# RFM69HW_SMA.net
KiCad netlist of a schematic drawn in EAGLE
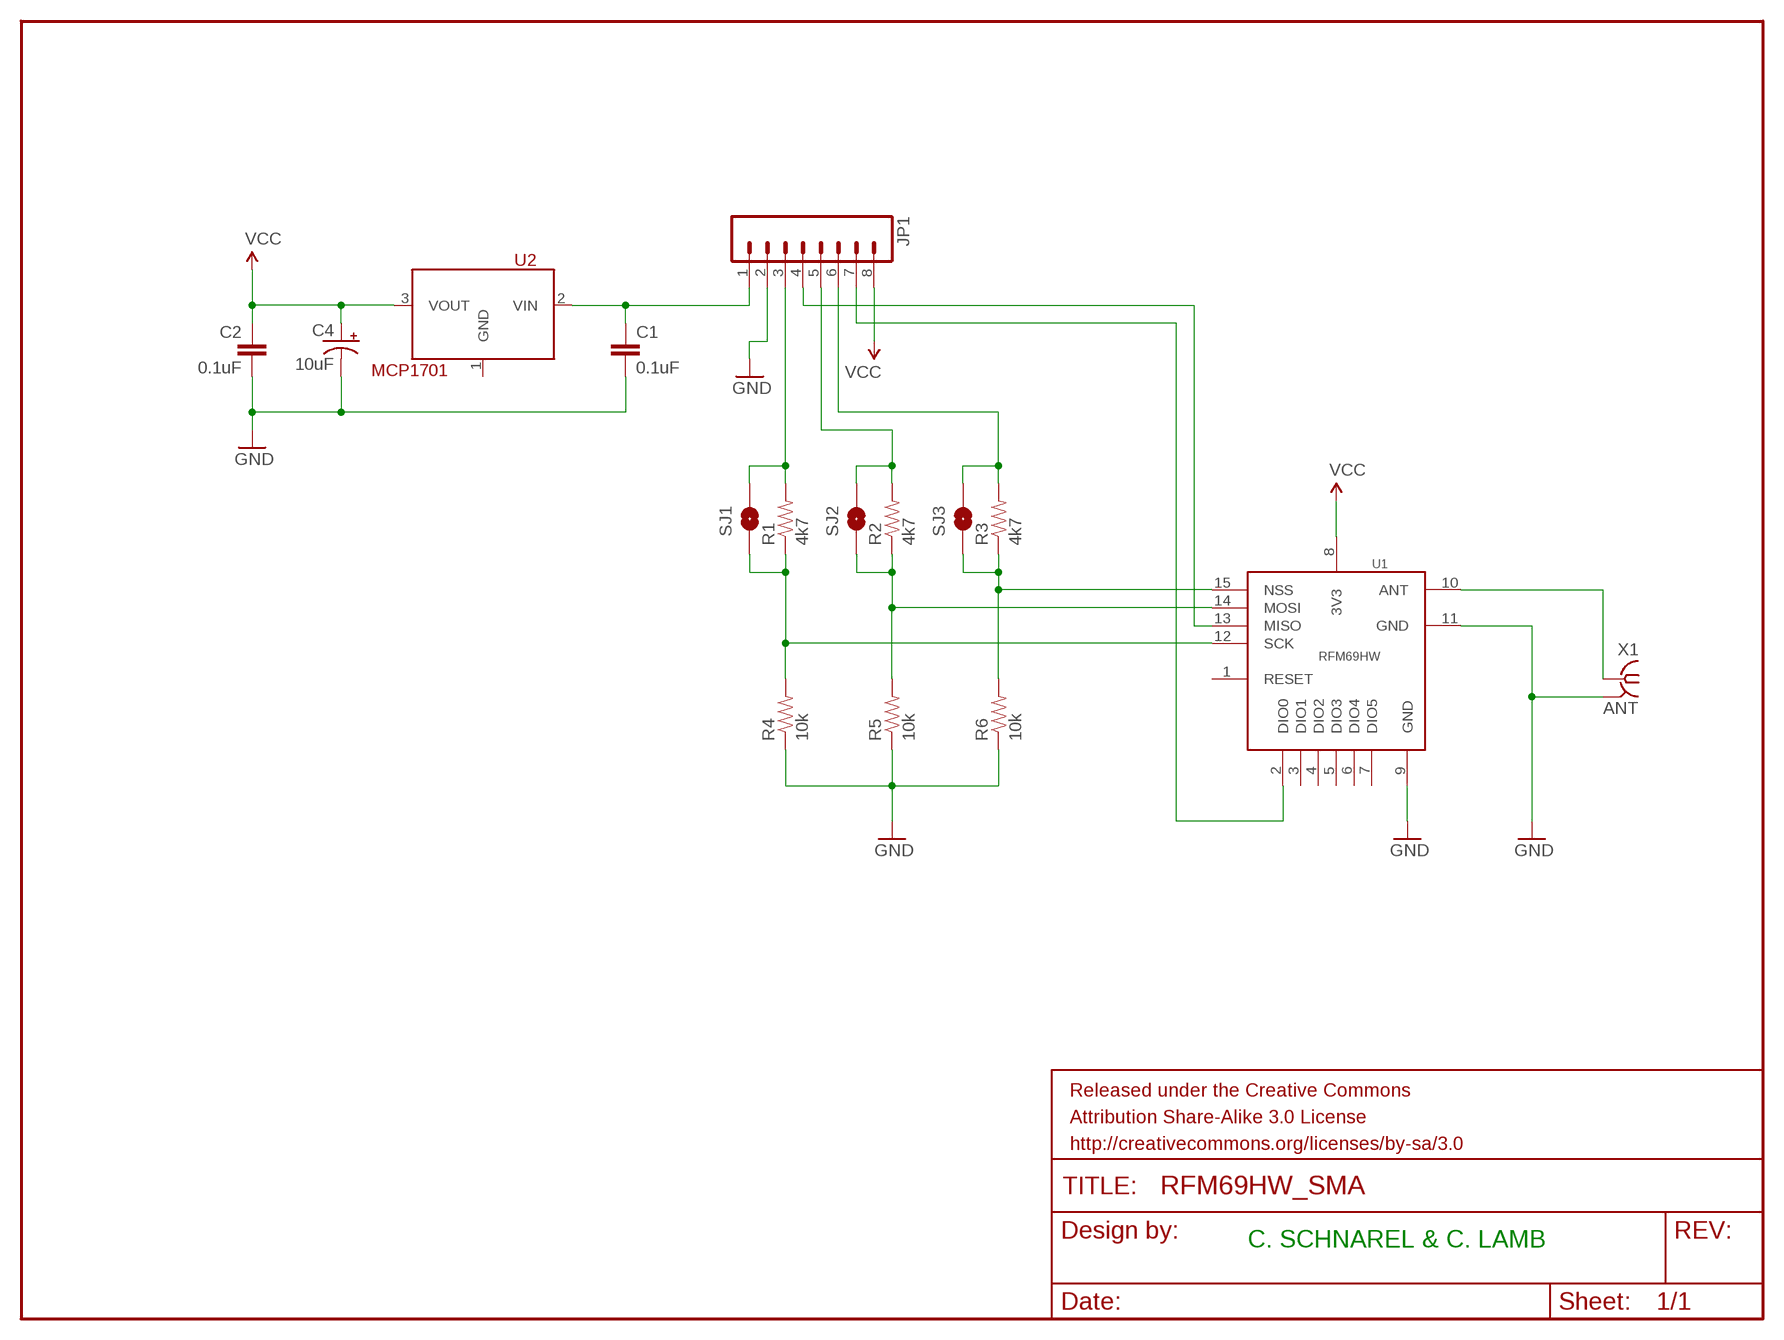
[diagram p0: schematic, sheet 1]

(export (version "E")
  (design (tool "Eeschema 10.0.6"))
  (components
    (comp (ref "C1")
      (value "0.1uF")
      (footprint "eagle-import:0805")
      (libsource (lib "eagle-import") (part "CAP0805"))
    )
    (comp (ref "C2")
      (value "0.1uF")
      (footprint "eagle-import:0805")
      (libsource (lib "eagle-import") (part "CAP0805"))
    )
    (comp (ref "C4")
      (value "10uF")
      (footprint "eagle-import:0805-POL")
      (libsource (lib "eagle-import") (part "CAP_POL0805"))
    )
    (comp (ref "FRAME1")
      (value "FRAME-LETTER")
      (footprint "eagle-import:CREATIVE_COMMONS")
      (libsource (lib "eagle-import") (part "FRAME-LETTER"))
    )
    (comp (ref "JP1")
      (value "M08LONGPADS")
      (footprint "eagle-import:1X08_LONGPADS")
      (libsource (lib "eagle-import") (part "M08LONGPADS"))
    )
    (comp (ref "R1")
      (value "4k7")
      (footprint "eagle-import:0805")
      (libsource (lib "eagle-import") (part "RESISTOR0805-RES"))
    )
    (comp (ref "R2")
      (value "4k7")
      (footprint "eagle-import:0805")
      (libsource (lib "eagle-import") (part "RESISTOR0805-RES"))
    )
    (comp (ref "R3")
      (value "4k7")
      (footprint "eagle-import:0805")
      (libsource (lib "eagle-import") (part "RESISTOR0805-RES"))
    )
    (comp (ref "R4")
      (value "10k")
      (footprint "eagle-import:0805")
      (libsource (lib "eagle-import") (part "RESISTOR0805-RES"))
    )
    (comp (ref "R5")
      (value "10k")
      (footprint "eagle-import:0805")
      (libsource (lib "eagle-import") (part "RESISTOR0805-RES"))
    )
    (comp (ref "R6")
      (value "10k")
      (footprint "eagle-import:0805")
      (libsource (lib "eagle-import") (part "RESISTOR0805-RES"))
    )
    (comp (ref "SJ1")
      (value "SOLDERJUMPERNO")
      (footprint "eagle-import:SJ_2S-NO")
      (libsource (lib "eagle-import") (part "SOLDERJUMPERNO"))
    )
    (comp (ref "SJ2")
      (value "SOLDERJUMPERNO")
      (footprint "eagle-import:SJ_2S-NO")
      (libsource (lib "eagle-import") (part "SOLDERJUMPERNO"))
    )
    (comp (ref "SJ3")
      (value "SOLDERJUMPERNO")
      (footprint "eagle-import:SJ_2S-NO")
      (libsource (lib "eagle-import") (part "SOLDERJUMPERNO"))
    )
    (comp (ref "U1")
      (value "RFM69HW")
      (footprint "eagle-import:RFM69")
      (libsource (lib "eagle-import") (part "RFM69HW"))
    )
    (comp (ref "U2")
      (value "MCP1701")
      (footprint "eagle-import:SOT-89")
      (libsource (lib "eagle-import") (part "MCP1701"))
    )
    (comp (ref "X1")
      (value "ANT")
      (footprint "eagle-import:TE-SMA-JACK-STR")
      (fields (field (name "MF") "TE Connectivity") (field (name "MPN") "5-1814832-1"))
      (libsource (lib "eagle-import") (part "TE-SMA-JACK-STR"))
    )
  )
  (nets
    (net (code "1") (name "GND") (class "Default")
      (node (ref "C1") (pin "2") (pinfunction "2_2") (pintype "passive"))
      (node (ref "C2") (pin "2") (pinfunction "2_2") (pintype "passive"))
      (node (ref "C4") (pin "2") (pinfunction "-_2") (pintype "passive"))
      (node (ref "JP1") (pin "2") (pinfunction "2_2") (pintype "passive"))
      (node (ref "R4") (pin "1") (pinfunction "1_1") (pintype "passive"))
      (node (ref "R5") (pin "1") (pinfunction "1_1") (pintype "passive"))
      (node (ref "R6") (pin "1") (pinfunction "1_1") (pintype "passive"))
      (node (ref "U1") (pin "11") (pinfunction "GND_11") (pintype "bidirectional"))
      (node (ref "U1") (pin "9") (pinfunction "GND_9") (pintype "bidirectional"))
      (node (ref "X1") (pin "2") (pinfunction "2_2") (pintype "passive"))
      (node (ref "X1") (pin "3") (pinfunction "2_3") (pintype "passive"))
      (node (ref "X1") (pin "4") (pinfunction "2_4") (pintype "passive"))
      (node (ref "X1") (pin "5") (pinfunction "2_5") (pintype "passive"))
    )
    (net (code "2") (name "Net-(JP1-Pad3)") (class "Default")
      (node (ref "JP1") (pin "3") (pinfunction "3_3") (pintype "passive"))
      (node (ref "R1") (pin "2") (pinfunction "2_2") (pintype "passive"))
      (node (ref "SJ1") (pin "2") (pinfunction "2_2") (pintype "passive"))
    )
    (net (code "3") (name "Net-(JP1-Pad5)") (class "Default")
      (node (ref "JP1") (pin "5") (pinfunction "5_5") (pintype "passive"))
      (node (ref "R2") (pin "2") (pinfunction "2_2") (pintype "passive"))
      (node (ref "SJ2") (pin "2") (pinfunction "2_2") (pintype "passive"))
    )
    (net (code "4") (name "Net-(JP1-Pad6)") (class "Default")
      (node (ref "JP1") (pin "6") (pinfunction "6_6") (pintype "passive"))
      (node (ref "R3") (pin "2") (pinfunction "2_2") (pintype "passive"))
      (node (ref "SJ3") (pin "2") (pinfunction "2_2") (pintype "passive"))
    )
    (net (code "5") (name "Net-(U1-ANT)") (class "Default")
      (node (ref "U1") (pin "10") (pinfunction "ANT_10") (pintype "bidirectional"))
      (node (ref "X1") (pin "1") (pinfunction "1_1") (pintype "passive"))
    )
    (net (code "6") (name "Net-(U1-DIO0)") (class "Default")
      (node (ref "JP1") (pin "7") (pinfunction "7_7") (pintype "passive"))
      (node (ref "U1") (pin "2") (pinfunction "DIO0_2") (pintype "bidirectional"))
    )
    (net (code "7") (name "Net-(U1-MISO)") (class "Default")
      (node (ref "JP1") (pin "4") (pinfunction "4_4") (pintype "passive"))
      (node (ref "U1") (pin "13") (pinfunction "MISO_13") (pintype "bidirectional"))
    )
    (net (code "8") (name "Net-(U1-MOSI)") (class "Default")
      (node (ref "R2") (pin "1") (pinfunction "1_1") (pintype "passive"))
      (node (ref "R5") (pin "2") (pinfunction "2_2") (pintype "passive"))
      (node (ref "SJ2") (pin "1") (pinfunction "1_1") (pintype "passive"))
      (node (ref "U1") (pin "14") (pinfunction "MOSI_14") (pintype "bidirectional"))
    )
    (net (code "9") (name "Net-(U1-NSS)") (class "Default")
      (node (ref "R3") (pin "1") (pinfunction "1_1") (pintype "passive"))
      (node (ref "R6") (pin "2") (pinfunction "2_2") (pintype "passive"))
      (node (ref "SJ3") (pin "1") (pinfunction "1_1") (pintype "passive"))
      (node (ref "U1") (pin "15") (pinfunction "NSS_15") (pintype "bidirectional"))
    )
    (net (code "10") (name "Net-(U1-SCK)") (class "Default")
      (node (ref "R1") (pin "1") (pinfunction "1_1") (pintype "passive"))
      (node (ref "R4") (pin "2") (pinfunction "2_2") (pintype "passive"))
      (node (ref "SJ1") (pin "1") (pinfunction "1_1") (pintype "passive"))
      (node (ref "U1") (pin "12") (pinfunction "SCK_12") (pintype "bidirectional"))
    )
    (net (code "11") (name "Net-(U2-VIN)") (class "Default")
      (node (ref "C1") (pin "1") (pinfunction "1_1") (pintype "passive"))
      (node (ref "JP1") (pin "1") (pinfunction "1_1") (pintype "passive"))
      (node (ref "U2") (pin "2") (pinfunction "VIN_2") (pintype "bidirectional"))
    )
    (net (code "12") (name "VCC") (class "Default")
      (node (ref "C2") (pin "1") (pinfunction "1_1") (pintype "passive"))
      (node (ref "C4") (pin "1") (pinfunction "+_1") (pintype "passive"))
      (node (ref "JP1") (pin "8") (pinfunction "8_8") (pintype "passive"))
      (node (ref "U1") (pin "8") (pinfunction "3V3_8") (pintype "bidirectional"))
      (node (ref "U2") (pin "3") (pinfunction "VOUT_3") (pintype "bidirectional"))
    )
    (net (code "13") (name "unconnected-(U1-DIO1-Pad3)") (class "Default")
      (node (ref "U1") (pin "3") (pinfunction "DIO1_3") (pintype "bidirectional"))
    )
    (net (code "14") (name "unconnected-(U1-DIO2-Pad4)") (class "Default")
      (node (ref "U1") (pin "4") (pinfunction "DIO2_4") (pintype "bidirectional"))
    )
    (net (code "15") (name "unconnected-(U1-DIO3-Pad5)") (class "Default")
      (node (ref "U1") (pin "5") (pinfunction "DIO3_5") (pintype "bidirectional"))
    )
    (net (code "16") (name "unconnected-(U1-DIO4-Pad6)") (class "Default")
      (node (ref "U1") (pin "6") (pinfunction "DIO4_6") (pintype "bidirectional"))
    )
    (net (code "17") (name "unconnected-(U1-DIO5-Pad7)") (class "Default")
      (node (ref "U1") (pin "7") (pinfunction "DIO5_7") (pintype "bidirectional"))
    )
    (net (code "18") (name "unconnected-(U1-RESET-Pad1)") (class "Default")
      (node (ref "U1") (pin "1") (pinfunction "RESET_1") (pintype "bidirectional"))
    )
    (net (code "19") (name "unconnected-(U2-GND-Pad1)") (class "Default")
      (node (ref "U2") (pin "1") (pinfunction "GND_1") (pintype "bidirectional"))
    )
  )
)
